# lpmon.net
KiCad netlist of a schematic drawn in EAGLE
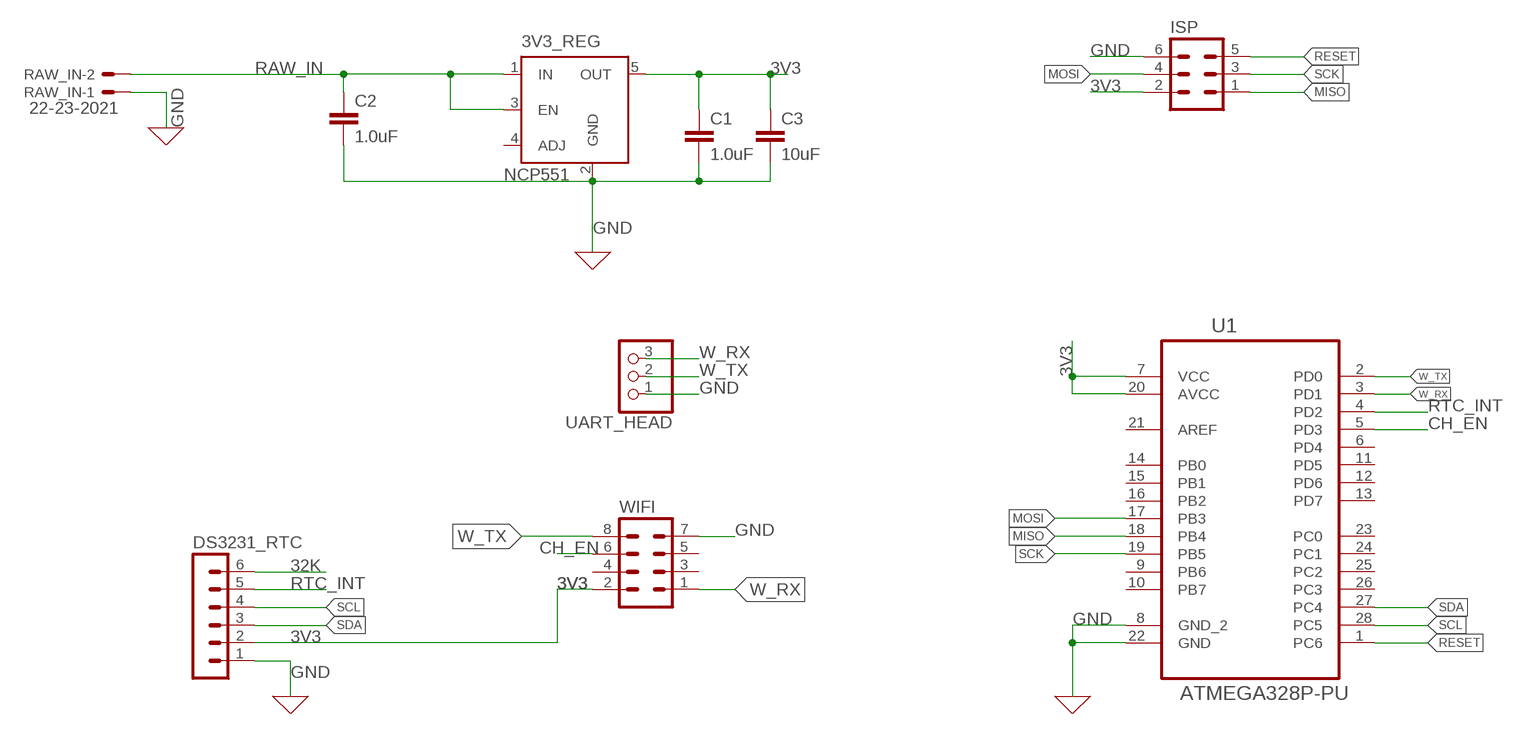
[diagram p0: schematic, sheet 1]

(export (version "E")
  (design (tool "Eeschema 10.0.6"))
  (components
    (comp (ref "3V3_REG")
      (value "NCP551")
      (footprint "eagle-import:SOT23-5")
      (fields (field (name "MF") "ALTERA CORPORATION") (field (name "MPN") "MIC5219BM5 TR"))
      (libsource (lib "eagle-import") (part "MIC5219BM5"))
    )
    (comp (ref "C1")
      (value "1.0uF")
      (footprint "eagle-import:C2.5-2")
      (libsource (lib "eagle-import") (part "C2.5/2"))
    )
    (comp (ref "C2")
      (value "1.0uF")
      (footprint "eagle-import:C2.5-2")
      (libsource (lib "eagle-import") (part "C2.5/2"))
    )
    (comp (ref "C3")
      (value "10uF")
      (footprint "eagle-import:C2.5-2")
      (libsource (lib "eagle-import") (part "C2.5/2"))
    )
    (comp (ref "DS3231_RTC")
      (value "MA06-1")
      (footprint "eagle-import:MA06-1")
      (libsource (lib "eagle-import") (part "MA06-1"))
    )
    (comp (ref "ISP")
      (value "MA03-2")
      (footprint "eagle-import:MA03-2")
      (libsource (lib "eagle-import") (part "MA03-2"))
    )
    (comp (ref "RAW_IN")
      (value "22-23-2021")
      (footprint "eagle-import:22-23-2021")
      (fields (field (name "MF") "MOLEX"))
      (libsource (lib "eagle-import") (part "22-23-2021"))
    )
    (comp (ref "U1")
      (value "ATMEGA328P-PU")
      (footprint "eagle-import:DIP254P762X457-28")
      (libsource (lib "eagle-import") (part "ATMEGA328P-PU"))
    )
    (comp (ref "UART_HEAD")
      (value "PINHD-1X3")
      (footprint "eagle-import:1X03")
      (libsource (lib "eagle-import") (part "PINHD-1X3"))
    )
    (comp (ref "WIFI")
      (value "MA04-2")
      (footprint "eagle-import:MA04-2")
      (libsource (lib "eagle-import") (part "MA04-2"))
    )
  )
  (nets
    (net (code "1") (name "/3V3") (class "Default")
      (node (ref "3V3_REG") (pin "5") (pinfunction "OUT_5") (pintype "output"))
      (node (ref "C1") (pin "1") (pinfunction "1_1") (pintype "passive"))
      (node (ref "C3") (pin "1") (pinfunction "1_1") (pintype "passive"))
      (node (ref "DS3231_RTC") (pin "2") (pinfunction "2_2") (pintype "passive"))
      (node (ref "ISP") (pin "2") (pinfunction "2_2") (pintype "passive"))
      (node (ref "U1") (pin "20") (pinfunction "AVCC_20") (pintype "power_in"))
      (node (ref "U1") (pin "7") (pinfunction "VCC_7") (pintype "power_in"))
      (node (ref "WIFI") (pin "2") (pinfunction "2_2") (pintype "passive"))
    )
    (net (code "2") (name "/32K") (class "Default")
      (node (ref "DS3231_RTC") (pin "6") (pinfunction "6_6") (pintype "passive"))
    )
    (net (code "3") (name "/CH_EN") (class "Default")
      (node (ref "U1") (pin "5") (pinfunction "PD3_5") (pintype "bidirectional"))
      (node (ref "WIFI") (pin "6") (pinfunction "6_6") (pintype "passive"))
    )
    (net (code "4") (name "/RAW_IN") (class "Default")
      (node (ref "3V3_REG") (pin "1") (pinfunction "IN_1") (pintype "input"))
      (node (ref "3V3_REG") (pin "3") (pinfunction "EN_3") (pintype "input"))
      (node (ref "C2") (pin "1") (pinfunction "1_1") (pintype "passive"))
      (node (ref "RAW_IN") (pin "2") (pinfunction "S_2") (pintype "passive"))
    )
    (net (code "5") (name "/RTC_INT") (class "Default")
      (node (ref "DS3231_RTC") (pin "5") (pinfunction "5_5") (pintype "passive"))
      (node (ref "U1") (pin "4") (pinfunction "PD2_4") (pintype "bidirectional"))
    )
    (net (code "6") (name "GND") (class "Default")
      (node (ref "3V3_REG") (pin "2") (pinfunction "GND_2") (pintype "power_in"))
      (node (ref "C1") (pin "2") (pinfunction "2_2") (pintype "passive"))
      (node (ref "C2") (pin "2") (pinfunction "2_2") (pintype "passive"))
      (node (ref "C3") (pin "2") (pinfunction "2_2") (pintype "passive"))
      (node (ref "DS3231_RTC") (pin "1") (pinfunction "1_1") (pintype "passive"))
      (node (ref "ISP") (pin "6") (pinfunction "6_6") (pintype "passive"))
      (node (ref "RAW_IN") (pin "1") (pinfunction "S_1") (pintype "passive"))
      (node (ref "U1") (pin "22") (pinfunction "GND_22") (pintype "passive"))
      (node (ref "U1") (pin "8") (pinfunction "GND_2_8") (pintype "passive"))
      (node (ref "UART_HEAD") (pin "1") (pinfunction "1_1") (pintype "passive"))
      (node (ref "WIFI") (pin "7") (pinfunction "7_7") (pintype "passive"))
    )
    (net (code "7") (name "MISO") (class "Default")
      (node (ref "ISP") (pin "1") (pinfunction "1_1") (pintype "passive"))
      (node (ref "U1") (pin "18") (pinfunction "PB4_18") (pintype "bidirectional"))
    )
    (net (code "8") (name "MOSI") (class "Default")
      (node (ref "ISP") (pin "4") (pinfunction "4_4") (pintype "passive"))
      (node (ref "U1") (pin "17") (pinfunction "PB3_17") (pintype "bidirectional"))
    )
    (net (code "9") (name "RESET") (class "Default")
      (node (ref "ISP") (pin "5") (pinfunction "5_5") (pintype "passive"))
      (node (ref "U1") (pin "1") (pinfunction "PC6_1") (pintype "bidirectional"))
    )
    (net (code "10") (name "SCK") (class "Default")
      (node (ref "ISP") (pin "3") (pinfunction "3_3") (pintype "passive"))
      (node (ref "U1") (pin "19") (pinfunction "PB5_19") (pintype "bidirectional"))
    )
    (net (code "11") (name "SCL") (class "Default")
      (node (ref "DS3231_RTC") (pin "4") (pinfunction "4_4") (pintype "passive"))
      (node (ref "U1") (pin "28") (pinfunction "PC5_28") (pintype "bidirectional"))
    )
    (net (code "12") (name "SDA") (class "Default")
      (node (ref "DS3231_RTC") (pin "3") (pinfunction "3_3") (pintype "passive"))
      (node (ref "U1") (pin "27") (pinfunction "PC4_27") (pintype "bidirectional"))
    )
    (net (code "13") (name "W_RX") (class "Default")
      (node (ref "U1") (pin "3") (pinfunction "PD1_3") (pintype "bidirectional"))
      (node (ref "UART_HEAD") (pin "3") (pinfunction "3_3") (pintype "passive"))
      (node (ref "WIFI") (pin "1") (pinfunction "1_1") (pintype "passive"))
    )
    (net (code "14") (name "W_TX") (class "Default")
      (node (ref "U1") (pin "2") (pinfunction "PD0_2") (pintype "bidirectional"))
      (node (ref "UART_HEAD") (pin "2") (pinfunction "2_2") (pintype "passive"))
      (node (ref "WIFI") (pin "8") (pinfunction "8_8") (pintype "passive"))
    )
    (net (code "15") (name "unconnected-(3V3_REG-ADJ-Pad4)") (class "Default")
      (node (ref "3V3_REG") (pin "4") (pinfunction "ADJ_4") (pintype "passive"))
    )
    (net (code "16") (name "unconnected-(U1-AREF-Pad21)") (class "Default")
      (node (ref "U1") (pin "21") (pinfunction "AREF_21") (pintype "input"))
    )
    (net (code "17") (name "unconnected-(U1-PB0-Pad14)") (class "Default")
      (node (ref "U1") (pin "14") (pinfunction "PB0_14") (pintype "bidirectional"))
    )
    (net (code "18") (name "unconnected-(U1-PB1-Pad15)") (class "Default")
      (node (ref "U1") (pin "15") (pinfunction "PB1_15") (pintype "bidirectional"))
    )
    (net (code "19") (name "unconnected-(U1-PB2-Pad16)") (class "Default")
      (node (ref "U1") (pin "16") (pinfunction "PB2_16") (pintype "bidirectional"))
    )
    (net (code "20") (name "unconnected-(U1-PB6-Pad9)") (class "Default")
      (node (ref "U1") (pin "9") (pinfunction "PB6_9") (pintype "bidirectional"))
    )
    (net (code "21") (name "unconnected-(U1-PB7-Pad10)") (class "Default")
      (node (ref "U1") (pin "10") (pinfunction "PB7_10") (pintype "bidirectional"))
    )
    (net (code "22") (name "unconnected-(U1-PC0-Pad23)") (class "Default")
      (node (ref "U1") (pin "23") (pinfunction "PC0_23") (pintype "bidirectional"))
    )
    (net (code "23") (name "unconnected-(U1-PC1-Pad24)") (class "Default")
      (node (ref "U1") (pin "24") (pinfunction "PC1_24") (pintype "bidirectional"))
    )
    (net (code "24") (name "unconnected-(U1-PC2-Pad25)") (class "Default")
      (node (ref "U1") (pin "25") (pinfunction "PC2_25") (pintype "bidirectional"))
    )
    (net (code "25") (name "unconnected-(U1-PC3-Pad26)") (class "Default")
      (node (ref "U1") (pin "26") (pinfunction "PC3_26") (pintype "bidirectional"))
    )
    (net (code "26") (name "unconnected-(U1-PD4-Pad6)") (class "Default")
      (node (ref "U1") (pin "6") (pinfunction "PD4_6") (pintype "bidirectional"))
    )
    (net (code "27") (name "unconnected-(U1-PD5-Pad11)") (class "Default")
      (node (ref "U1") (pin "11") (pinfunction "PD5_11") (pintype "bidirectional"))
    )
    (net (code "28") (name "unconnected-(U1-PD6-Pad12)") (class "Default")
      (node (ref "U1") (pin "12") (pinfunction "PD6_12") (pintype "bidirectional"))
    )
    (net (code "29") (name "unconnected-(U1-PD7-Pad13)") (class "Default")
      (node (ref "U1") (pin "13") (pinfunction "PD7_13") (pintype "bidirectional"))
    )
    (net (code "30") (name "unconnected-(WIFI-Pad3)") (class "Default")
      (node (ref "WIFI") (pin "3") (pinfunction "3_3") (pintype "passive"))
    )
    (net (code "31") (name "unconnected-(WIFI-Pad4)") (class "Default")
      (node (ref "WIFI") (pin "4") (pinfunction "4_4") (pintype "passive"))
    )
    (net (code "32") (name "unconnected-(WIFI-Pad5)") (class "Default")
      (node (ref "WIFI") (pin "5") (pinfunction "5_5") (pintype "passive"))
    )
  )
)
